# Mosquito1.net
KiCad netlist of a schematic drawn in EAGLE
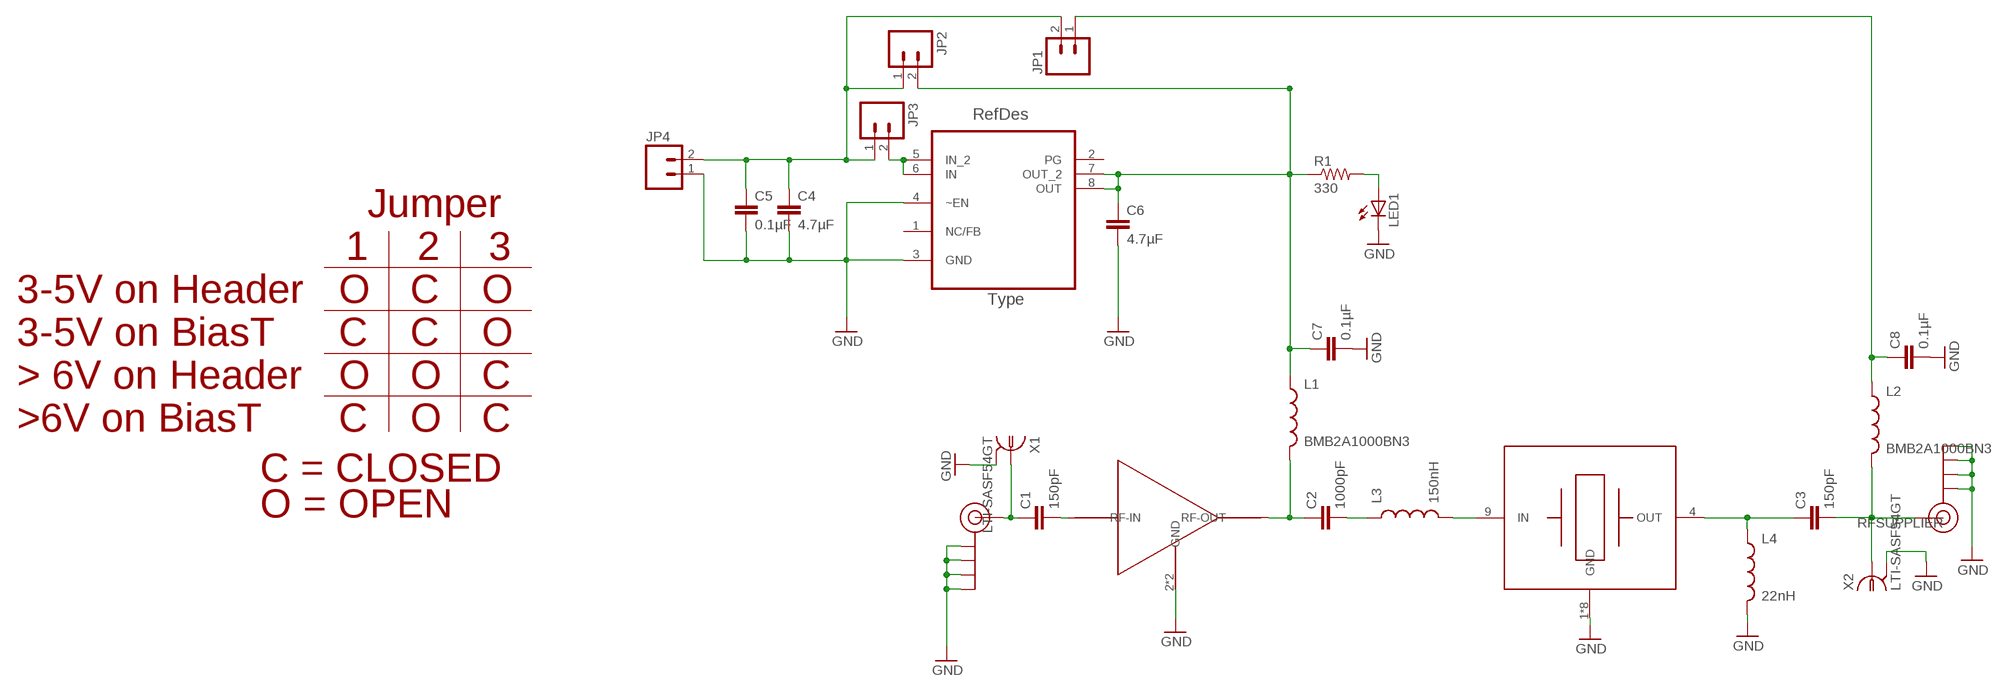
[diagram p0: schematic, sheet 1]

(export (version "E")
  (design (tool "Eeschema 10.0.6"))
  (components
    (comp (ref "C1")
      (value "150pF")
      (footprint "eagle-import:0603-CAP")
      (libsource (lib "eagle-import") (part "CAP0603-CAP"))
    )
    (comp (ref "C2")
      (value "1000pF")
      (footprint "eagle-import:0603-CAP")
      (libsource (lib "eagle-import") (part "CAP0603-CAP"))
    )
    (comp (ref "C3")
      (value "150pF")
      (footprint "eagle-import:0603-CAP")
      (libsource (lib "eagle-import") (part "CAP0603-CAP"))
    )
    (comp (ref "C4")
      (value "4.7µF")
      (footprint "eagle-import:0805")
      (libsource (lib "eagle-import") (part "CAP0805"))
    )
    (comp (ref "C5")
      (value "0.1µF")
      (footprint "eagle-import:0603-CAP")
      (libsource (lib "eagle-import") (part "CAP0603-CAP"))
    )
    (comp (ref "C6")
      (value "4.7µF")
      (footprint "eagle-import:0805")
      (libsource (lib "eagle-import") (part "CAP0805"))
    )
    (comp (ref "C7")
      (value "0.1µF")
      (footprint "eagle-import:0603-CAP")
      (libsource (lib "eagle-import") (part "CAP0603-CAP"))
    )
    (comp (ref "C8")
      (value "0.1µF")
      (footprint "eagle-import:0603-CAP")
      (libsource (lib "eagle-import") (part "CAP0603-CAP"))
    )
    (comp (ref "IN")
      (value "SMA_EDGE")
      (footprint "eagle-import:SMA-EDGE")
      (libsource (lib "eagle-import") (part "SMA_EDGE"))
    )
    (comp (ref "JP1")
      (value "M02PTH")
      (footprint "eagle-import:1X02")
      (libsource (lib "eagle-import") (part "M02PTH"))
    )
    (comp (ref "JP2")
      (value "M02PTH")
      (footprint "eagle-import:1X02")
      (libsource (lib "eagle-import") (part "M02PTH"))
    )
    (comp (ref "JP3")
      (value "M02PTH")
      (footprint "eagle-import:1X02")
      (libsource (lib "eagle-import") (part "M02PTH"))
    )
    (comp (ref "JP4")
      (value "M02PTH")
      (footprint "eagle-import:1X02")
      (libsource (lib "eagle-import") (part "M02PTH"))
    )
    (comp (ref "L1")
      (value "BMB2A1000BN3")
      (footprint "eagle-import:0805")
      (libsource (lib "eagle-import") (part "INDUCTOR0805"))
    )
    (comp (ref "L2")
      (value "BMB2A1000BN3")
      (footprint "eagle-import:0805")
      (libsource (lib "eagle-import") (part "INDUCTOR0805"))
    )
    (comp (ref "L3")
      (value "150nH")
      (footprint "eagle-import:0603")
      (libsource (lib "eagle-import") (part "SparkFun-Passives_INDUCTOR0603"))
    )
    (comp (ref "L4")
      (value "22nH")
      (footprint "eagle-import:0603")
      (libsource (lib "eagle-import") (part "SparkFun-Passives_INDUCTOR0603"))
    )
    (comp (ref "LED1")
      (value "LEDCHIP-LED0603")
      (footprint "eagle-import:CHIP-LED0603")
      (libsource (lib "eagle-import") (part "LEDCHIP-LED0603"))
    )
    (comp (ref "OUT")
      (value "SMA_EDGE")
      (footprint "eagle-import:SMA-EDGE")
      (libsource (lib "eagle-import") (part "SMA_EDGE"))
    )
    (comp (ref "R1")
      (value "330")
      (footprint "eagle-import:0402-RES")
      (libsource (lib "eagle-import") (part "RESISTOR0402-RES"))
    )
    (comp (ref "SAW")
      (value "856929")
      (footprint "eagle-import:TRIQUINT_856929")
      (libsource (lib "eagle-import") (part "856929"))
    )
    (comp (ref "U$2")
      (value "PSA4-5043+")
      (footprint "eagle-import:PSA4-5043+")
      (libsource (lib "eagle-import") (part "PSA4-5043+"))
    )
    (comp (ref "U1")
      (value "TPS76633D")
      (footprint "eagle-import:SOIC127P600X175-8N")
      (libsource (lib "eagle-import") (part "TPS76633D"))
    )
    (comp (ref "X1")
      (value "LTI-SASF54GT")
      (footprint "eagle-import:LTI-SASF54GT")
      (libsource (lib "eagle-import") (part "LTI-SASF54GT"))
    )
    (comp (ref "X2")
      (value "LTI-SASF54GT")
      (footprint "eagle-import:LTI-SASF54GT")
      (libsource (lib "eagle-import") (part "LTI-SASF54GT"))
    )
  )
  (nets
    (net (code "1") (name "GND") (class "Default")
      (node (ref "C4") (pin "2") (pinfunction "2_2") (pintype "passive"))
      (node (ref "C5") (pin "2") (pinfunction "2_2") (pintype "passive"))
      (node (ref "C6") (pin "2") (pinfunction "2_2") (pintype "passive"))
      (node (ref "C7") (pin "2") (pinfunction "2_2") (pintype "passive"))
      (node (ref "C8") (pin "2") (pinfunction "2_2") (pintype "passive"))
      (node (ref "IN") (pin "GND@0") (pinfunction "GND_GND@0") (pintype "bidirectional"))
      (node (ref "IN") (pin "GND@1") (pinfunction "GND_GND@1") (pintype "bidirectional"))
      (node (ref "IN") (pin "GND@2") (pinfunction "GND_GND@2") (pintype "bidirectional"))
      (node (ref "IN") (pin "GND@3") (pinfunction "GND_GND@3") (pintype "bidirectional"))
      (node (ref "JP4") (pin "1") (pinfunction "1_1") (pintype "passive"))
      (node (ref "L4") (pin "2") (pinfunction "2_2") (pintype "passive"))
      (node (ref "LED1") (pin "C") (pinfunction "C_C") (pintype "passive"))
      (node (ref "OUT") (pin "GND@0") (pinfunction "GND_GND@0") (pintype "bidirectional"))
      (node (ref "OUT") (pin "GND@1") (pinfunction "GND_GND@1") (pintype "bidirectional"))
      (node (ref "OUT") (pin "GND@2") (pinfunction "GND_GND@2") (pintype "bidirectional"))
      (node (ref "OUT") (pin "GND@3") (pinfunction "GND_GND@3") (pintype "bidirectional"))
      (node (ref "SAW") (pin "1") (pinfunction "GND_1") (pintype "bidirectional"))
      (node (ref "SAW") (pin "10") (pinfunction "GND_10") (pintype "bidirectional"))
      (node (ref "SAW") (pin "2") (pinfunction "GND_2") (pintype "bidirectional"))
      (node (ref "SAW") (pin "3") (pinfunction "GND_3") (pintype "bidirectional"))
      (node (ref "SAW") (pin "5") (pinfunction "GND_5") (pintype "bidirectional"))
      (node (ref "SAW") (pin "6") (pinfunction "GND_6") (pintype "bidirectional"))
      (node (ref "SAW") (pin "7") (pinfunction "GND_7") (pintype "bidirectional"))
      (node (ref "SAW") (pin "8") (pinfunction "GND_8") (pintype "bidirectional"))
      (node (ref "U$2") (pin "2") (pinfunction "GND_2") (pintype "bidirectional"))
      (node (ref "U$2") (pin "4") (pinfunction "GND_4") (pintype "bidirectional"))
      (node (ref "U1") (pin "3") (pinfunction "GND_3") (pintype "passive"))
      (node (ref "U1") (pin "4") (pinfunction "~{EN}_4") (pintype "input"))
      (node (ref "X1") (pin "2") (pinfunction "2_2") (pintype "passive"))
      (node (ref "X1") (pin "3") (pinfunction "2_3") (pintype "passive"))
      (node (ref "X1") (pin "4") (pinfunction "2_4") (pintype "passive"))
      (node (ref "X1") (pin "5") (pinfunction "2_5") (pintype "passive"))
      (node (ref "X2") (pin "2") (pinfunction "2_2") (pintype "passive"))
      (node (ref "X2") (pin "3") (pinfunction "2_3") (pintype "passive"))
      (node (ref "X2") (pin "4") (pinfunction "2_4") (pintype "passive"))
      (node (ref "X2") (pin "5") (pinfunction "2_5") (pintype "passive"))
    )
    (net (code "2") (name "Net-(C2-Pad2)") (class "Default")
      (node (ref "C2") (pin "2") (pinfunction "2_2") (pintype "passive"))
      (node (ref "L3") (pin "1") (pinfunction "1_1") (pintype "passive"))
    )
    (net (code "3") (name "Net-(C4-Pad1)") (class "Default")
      (node (ref "C4") (pin "1") (pinfunction "1_1") (pintype "passive"))
      (node (ref "C5") (pin "1") (pinfunction "1_1") (pintype "passive"))
      (node (ref "JP1") (pin "2") (pinfunction "2_2") (pintype "passive"))
      (node (ref "JP2") (pin "1") (pinfunction "1_1") (pintype "passive"))
      (node (ref "JP3") (pin "1") (pinfunction "1_1") (pintype "passive"))
      (node (ref "JP4") (pin "2") (pinfunction "2_2") (pintype "passive"))
    )
    (net (code "4") (name "Net-(C8-Pad1)") (class "Default")
      (node (ref "C8") (pin "1") (pinfunction "1_1") (pintype "passive"))
      (node (ref "JP1") (pin "1") (pinfunction "1_1") (pintype "passive"))
      (node (ref "L2") (pin "1") (pinfunction "1_1") (pintype "passive"))
    )
    (net (code "5") (name "Net-(IN-SIGNAL)") (class "Default")
      (node (ref "C1") (pin "1") (pinfunction "1_1") (pintype "passive"))
      (node (ref "IN") (pin "SIG") (pinfunction "SIGNAL_SIG") (pintype "bidirectional"))
      (node (ref "X1") (pin "1") (pinfunction "1_1") (pintype "passive"))
    )
    (net (code "6") (name "Net-(LED1-PadA)") (class "Default")
      (node (ref "LED1") (pin "A") (pinfunction "A_A") (pintype "passive"))
      (node (ref "R1") (pin "2") (pinfunction "2_2") (pintype "passive"))
    )
    (net (code "7") (name "Net-(OUT-SIGNAL)") (class "Default")
      (node (ref "C3") (pin "2") (pinfunction "2_2") (pintype "passive"))
      (node (ref "L2") (pin "2") (pinfunction "2_2") (pintype "passive"))
      (node (ref "OUT") (pin "SIG") (pinfunction "SIGNAL_SIG") (pintype "bidirectional"))
      (node (ref "X2") (pin "1") (pinfunction "1_1") (pintype "passive"))
    )
    (net (code "8") (name "Net-(SAW-IN)") (class "Default")
      (node (ref "L3") (pin "2") (pinfunction "2_2") (pintype "passive"))
      (node (ref "SAW") (pin "9") (pinfunction "IN_9") (pintype "input"))
    )
    (net (code "9") (name "Net-(SAW-OUT)") (class "Default")
      (node (ref "C3") (pin "1") (pinfunction "1_1") (pintype "passive"))
      (node (ref "L4") (pin "1") (pinfunction "1_1") (pintype "passive"))
      (node (ref "SAW") (pin "4") (pinfunction "OUT_4") (pintype "output"))
    )
    (net (code "10") (name "Net-(U$2-RF-IN)") (class "Default")
      (node (ref "C1") (pin "2") (pinfunction "2_2") (pintype "passive"))
      (node (ref "U$2") (pin "3") (pinfunction "RF-IN_3") (pintype "bidirectional"))
    )
    (net (code "11") (name "Net-(U$2-RF-OUT)") (class "Default")
      (node (ref "C2") (pin "1") (pinfunction "1_1") (pintype "passive"))
      (node (ref "L1") (pin "2") (pinfunction "2_2") (pintype "passive"))
      (node (ref "U$2") (pin "1") (pinfunction "RF-OUT_1") (pintype "bidirectional"))
    )
    (net (code "12") (name "Net-(U1-IN)") (class "Default")
      (node (ref "JP3") (pin "2") (pinfunction "2_2") (pintype "passive"))
      (node (ref "U1") (pin "5") (pinfunction "IN_2_5") (pintype "input"))
      (node (ref "U1") (pin "6") (pinfunction "IN_6") (pintype "input"))
    )
    (net (code "13") (name "Net-(U1-OUT)") (class "Default")
      (node (ref "C6") (pin "1") (pinfunction "1_1") (pintype "passive"))
      (node (ref "C7") (pin "1") (pinfunction "1_1") (pintype "passive"))
      (node (ref "JP2") (pin "2") (pinfunction "2_2") (pintype "passive"))
      (node (ref "L1") (pin "1") (pinfunction "1_1") (pintype "passive"))
      (node (ref "R1") (pin "1") (pinfunction "1_1") (pintype "passive"))
      (node (ref "U1") (pin "7") (pinfunction "OUT_2_7") (pintype "output"))
      (node (ref "U1") (pin "8") (pinfunction "OUT_8") (pintype "output"))
    )
    (net (code "14") (name "unconnected-(U1-NC{slash}FB-Pad1)") (class "Default")
      (node (ref "U1") (pin "1") (pinfunction "NC/FB_1") (pintype "no_connect"))
    )
    (net (code "15") (name "unconnected-(U1-PG-Pad2)") (class "Default")
      (node (ref "U1") (pin "2") (pinfunction "PG_2") (pintype "output"))
    )
  )
)
